# JouleMeter_new.net
KiCad netlist of a schematic drawn in EAGLE
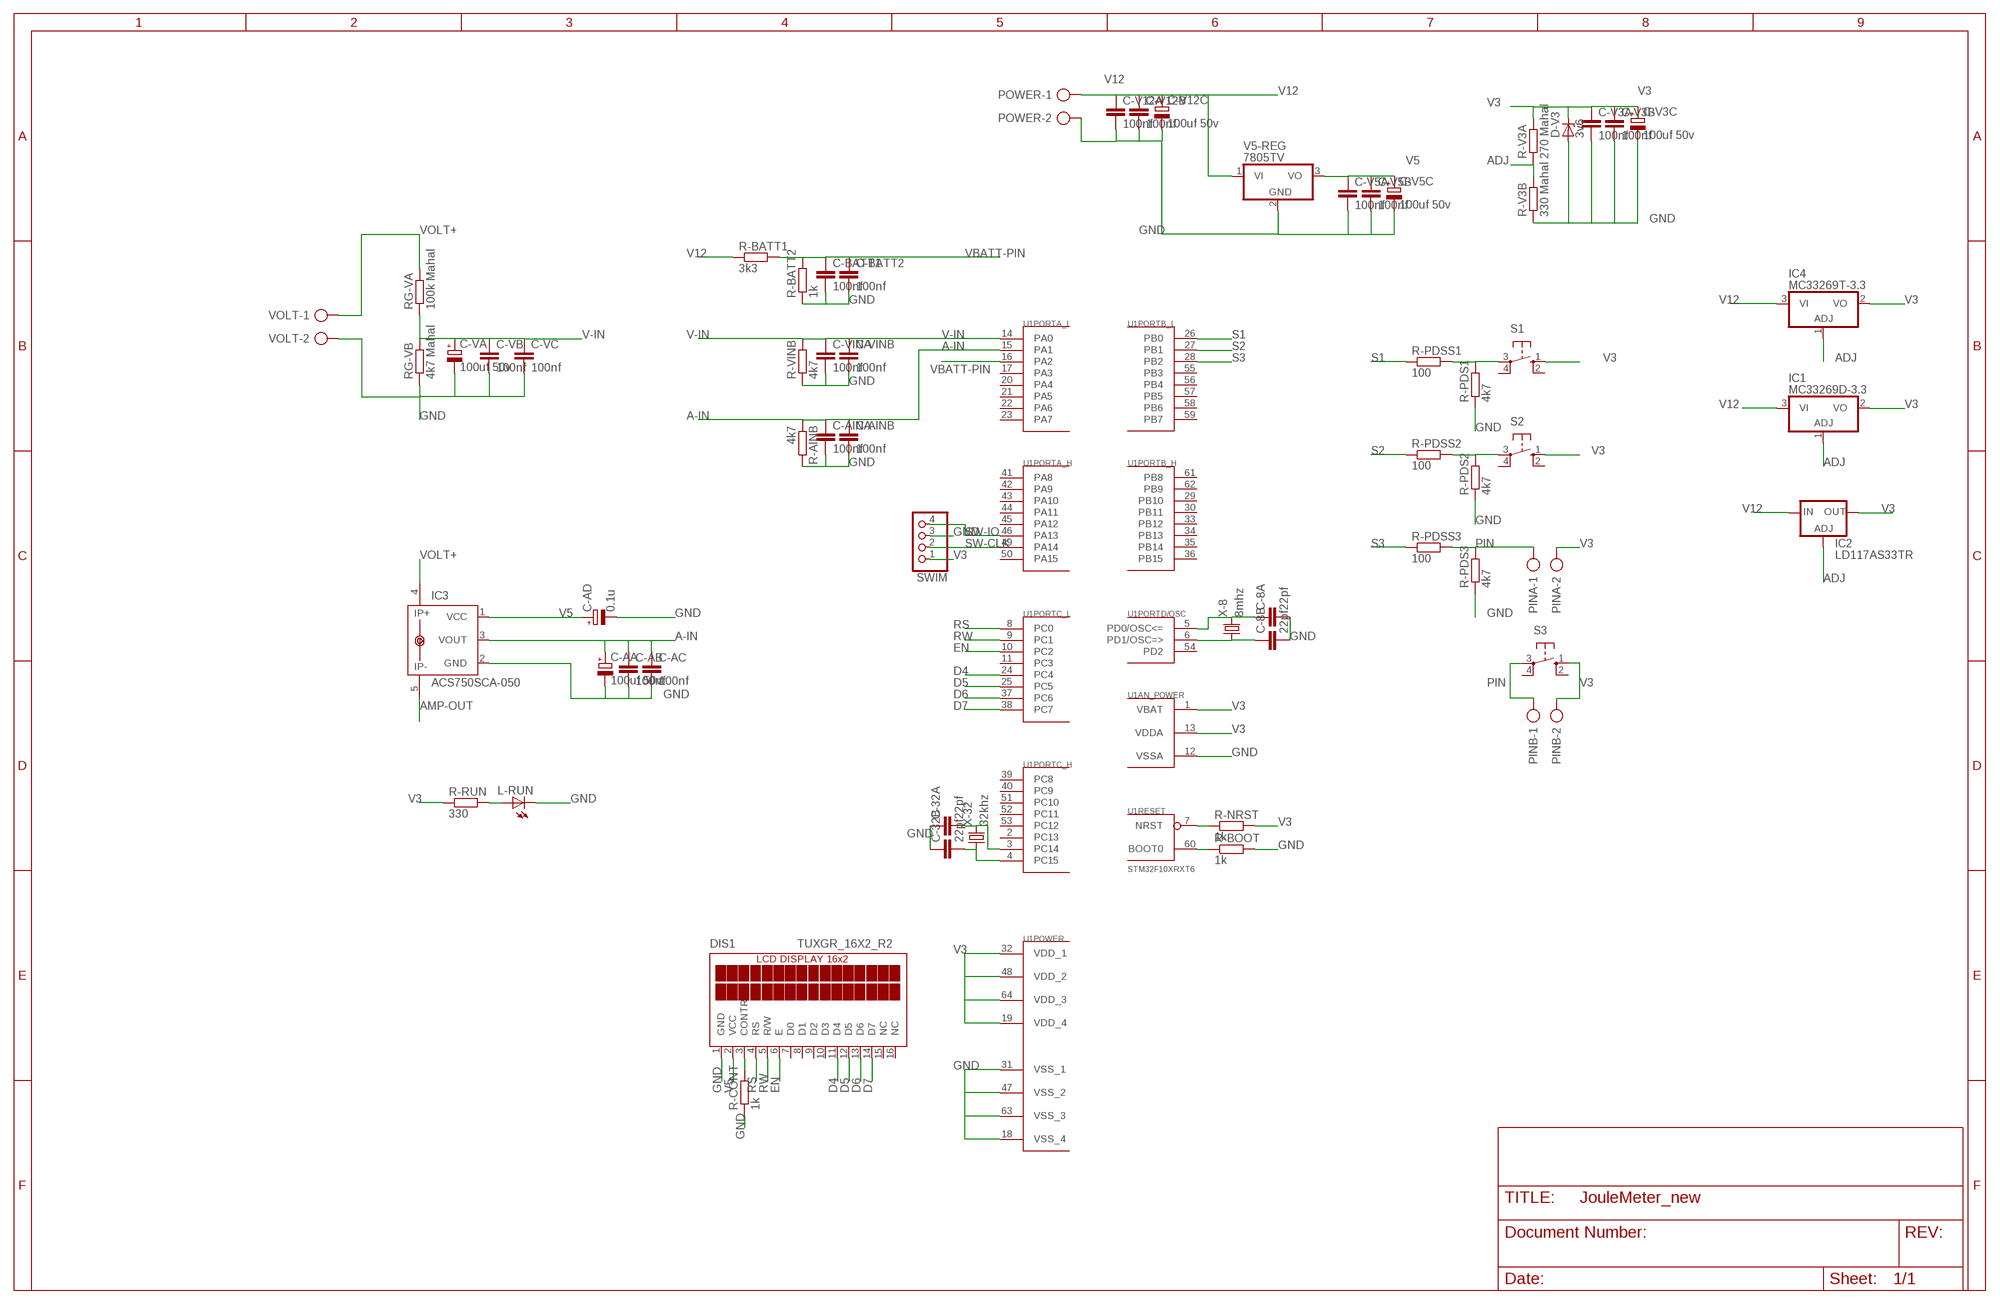
[diagram p0: schematic, sheet 1]

(export (version "E")
  (design (tool "Eeschema 10.0.6"))
  (components
    (comp (ref "C-8A")
      (value "22pf")
      (footprint "eagle-import:C025-024X044")
      (libsource (lib "eagle-import") (part "C-EU025-024X044"))
    )
    (comp (ref "C-8B")
      (value "22pf")
      (footprint "eagle-import:C025-024X044")
      (libsource (lib "eagle-import") (part "C-EU025-024X044"))
    )
    (comp (ref "C-32A")
      (value "22pf")
      (footprint "eagle-import:C025-024X044")
      (libsource (lib "eagle-import") (part "C-EU025-024X044"))
    )
    (comp (ref "C-32B")
      (value "22pf")
      (footprint "eagle-import:C025-024X044")
      (libsource (lib "eagle-import") (part "C-EU025-024X044"))
    )
    (comp (ref "C-AA")
      (value "100uf 50v")
      (footprint "eagle-import:E2-5")
      (libsource (lib "eagle-import") (part "CPOL-EUE2-5"))
    )
    (comp (ref "C-AB")
      (value "100nf")
      (footprint "eagle-import:C050-024X044")
      (libsource (lib "eagle-import") (part "C-EU050-024X044"))
    )
    (comp (ref "C-AC")
      (value "100nf")
      (footprint "eagle-import:C050-024X044")
      (libsource (lib "eagle-import") (part "C-EU050-024X044"))
    )
    (comp (ref "C-AD")
      (value "0.1u")
      (footprint "eagle-import:E2-5")
      (libsource (lib "eagle-import") (part "CPOL-EUE2-5"))
    )
    (comp (ref "C-AINA")
      (value "100nf")
      (footprint "eagle-import:C050-024X044")
      (libsource (lib "eagle-import") (part "C-EU050-024X044"))
    )
    (comp (ref "C-AINB")
      (value "100nf")
      (footprint "eagle-import:C050-024X044")
      (libsource (lib "eagle-import") (part "C-EU050-024X044"))
    )
    (comp (ref "C-BATT1")
      (value "100nf")
      (footprint "eagle-import:C050-024X044")
      (libsource (lib "eagle-import") (part "C-EU050-024X044"))
    )
    (comp (ref "C-BATT2")
      (value "100nf")
      (footprint "eagle-import:C050-024X044")
      (libsource (lib "eagle-import") (part "C-EU050-024X044"))
    )
    (comp (ref "C-V3A")
      (value "100nf")
      (footprint "eagle-import:C050-024X044")
      (libsource (lib "eagle-import") (part "C-EU050-024X044"))
    )
    (comp (ref "C-V3B")
      (value "100nf")
      (footprint "eagle-import:C050-024X044")
      (libsource (lib "eagle-import") (part "C-EU050-024X044"))
    )
    (comp (ref "C-V3C")
      (value "100uf 50v")
      (footprint "eagle-import:E5-5")
      (libsource (lib "eagle-import") (part "CPOL-EUE5-5"))
    )
    (comp (ref "C-V5A")
      (value "100nf")
      (footprint "eagle-import:C050-024X044")
      (libsource (lib "eagle-import") (part "C-EU050-024X044"))
    )
    (comp (ref "C-V5B")
      (value "100nf")
      (footprint "eagle-import:C050-024X044")
      (libsource (lib "eagle-import") (part "C-EU050-024X044"))
    )
    (comp (ref "C-V5C")
      (value "100uf 50v")
      (footprint "eagle-import:E5-5")
      (libsource (lib "eagle-import") (part "CPOL-EUE5-5"))
    )
    (comp (ref "C-V12A")
      (value "100nf")
      (footprint "eagle-import:C050-024X044")
      (libsource (lib "eagle-import") (part "C-EU050-024X044"))
    )
    (comp (ref "C-V12B")
      (value "100nf")
      (footprint "eagle-import:C050-024X044")
      (libsource (lib "eagle-import") (part "C-EU050-024X044"))
    )
    (comp (ref "C-V12C")
      (value "100uf 50v")
      (footprint "eagle-import:E5-5")
      (libsource (lib "eagle-import") (part "CPOL-EUE5-5"))
    )
    (comp (ref "C-VA")
      (value "100uf 50v")
      (footprint "eagle-import:E2-5")
      (libsource (lib "eagle-import") (part "CPOL-EUE2-5"))
    )
    (comp (ref "C-VB")
      (value "100nf")
      (footprint "eagle-import:C050-024X044")
      (libsource (lib "eagle-import") (part "C-EU050-024X044"))
    )
    (comp (ref "C-VC")
      (value "100nf")
      (footprint "eagle-import:C050-024X044")
      (libsource (lib "eagle-import") (part "C-EU050-024X044"))
    )
    (comp (ref "C-VINA")
      (value "100nf")
      (footprint "eagle-import:C050-024X044")
      (libsource (lib "eagle-import") (part "C-EU050-024X044"))
    )
    (comp (ref "C-VINB")
      (value "100nf")
      (footprint "eagle-import:C050-024X044")
      (libsource (lib "eagle-import") (part "C-EU050-024X044"))
    )
    (comp (ref "D-V3")
      (value "3v6")
      (footprint "eagle-import:ZDIO-7.5")
      (libsource (lib "eagle-import") (part "ZENER-DIODEZD-7.5"))
    )
    (comp (ref "DIS1")
      (value "TUXGR_16X2_R2")
      (footprint "eagle-import:TUXGR_16X2_R2")
      (libsource (lib "eagle-import") (part "TUXGR_16X2_R2"))
    )
    (comp (ref "IC1")
      (value "MC33269D-3.3")
      (footprint "eagle-import:DPACK")
      (libsource (lib "eagle-import") (part "MC33269?D-3.3"))
    )
    (comp (ref "IC2")
      (value "LD117AS33TR")
      (footprint "eagle-import:SOT223")
      (libsource (lib "eagle-import") (part "LD117A?S33TR"))
    )
    (comp (ref "IC3")
      (value "ACS750SCA-050")
      (footprint "eagle-import:ACS75050")
      (fields (field (name "MF") "ALLEGRO MICROSYSTEMS, INC."))
      (libsource (lib "eagle-import") (part "ACS750CA-050S"))
    )
    (comp (ref "IC4")
      (value "MC33269T-3.3")
      (footprint "eagle-import:TO220V")
      (libsource (lib "eagle-import") (part "MC33269?T-3.3"))
    )
    (comp (ref "L-RUN")
      (value "LED3MM")
      (footprint "eagle-import:LED3MM")
      (libsource (lib "eagle-import") (part "LED3MM"))
    )
    (comp (ref "PINA")
      (value "AK300/2")
      (footprint "eagle-import:AK300_2")
      (libsource (lib "eagle-import") (part "AK300/2"))
    )
    (comp (ref "PINB")
      (value "AK300/2")
      (footprint "eagle-import:AK300_2")
      (libsource (lib "eagle-import") (part "AK300/2"))
    )
    (comp (ref "POWER")
      (value "AK300/2")
      (footprint "eagle-import:AK300_2")
      (libsource (lib "eagle-import") (part "AK300/2"))
    )
    (comp (ref "R-AINB")
      (value "4k7")
      (footprint "eagle-import:0204_7")
      (libsource (lib "eagle-import") (part "R-EU_0204/7"))
    )
    (comp (ref "R-BATT1")
      (value "3k3")
      (footprint "eagle-import:0204_7")
      (libsource (lib "eagle-import") (part "R-EU_0204/7"))
    )
    (comp (ref "R-BATT2")
      (value "1k")
      (footprint "eagle-import:0204_7")
      (libsource (lib "eagle-import") (part "R-EU_0204/7"))
    )
    (comp (ref "R-BOOT")
      (value "1k")
      (footprint "eagle-import:0204_7")
      (libsource (lib "eagle-import") (part "R-EU_0204/7"))
    )
    (comp (ref "R-CONT")
      (value "1k")
      (footprint "eagle-import:0204_7")
      (libsource (lib "eagle-import") (part "R-EU_0204/7"))
    )
    (comp (ref "R-NRST")
      (value "1k")
      (footprint "eagle-import:0204_7")
      (libsource (lib "eagle-import") (part "R-EU_0204/7"))
    )
    (comp (ref "R-PDS1")
      (value "4k7")
      (footprint "eagle-import:0204_7")
      (libsource (lib "eagle-import") (part "R-EU_0204/7"))
    )
    (comp (ref "R-PDS2")
      (value "4k7")
      (footprint "eagle-import:0204_7")
      (libsource (lib "eagle-import") (part "R-EU_0204/7"))
    )
    (comp (ref "R-PDS3")
      (value "4k7")
      (footprint "eagle-import:0204_7")
      (libsource (lib "eagle-import") (part "R-EU_0204/7"))
    )
    (comp (ref "R-PDSS1")
      (value "100")
      (footprint "eagle-import:0204_7")
      (libsource (lib "eagle-import") (part "R-EU_0204/7"))
    )
    (comp (ref "R-PDSS2")
      (value "100")
      (footprint "eagle-import:0204_7")
      (libsource (lib "eagle-import") (part "R-EU_0204/7"))
    )
    (comp (ref "R-PDSS3")
      (value "100")
      (footprint "eagle-import:0204_7")
      (libsource (lib "eagle-import") (part "R-EU_0204/7"))
    )
    (comp (ref "R-RUN")
      (value "330")
      (footprint "eagle-import:0204_7")
      (libsource (lib "eagle-import") (part "R-EU_0204/7"))
    )
    (comp (ref "R-V3A")
      (value "270 Mahal")
      (footprint "eagle-import:0204_7")
      (libsource (lib "eagle-import") (part "R-EU_0204/7"))
    )
    (comp (ref "R-V3B")
      (value "330 Mahal")
      (footprint "eagle-import:0204_7")
      (libsource (lib "eagle-import") (part "R-EU_0204/7"))
    )
    (comp (ref "R-VINB")
      (value "4k7")
      (footprint "eagle-import:0204_7")
      (libsource (lib "eagle-import") (part "R-EU_0204/7"))
    )
    (comp (ref "RG-VA")
      (value "100k Mahal")
      (footprint "eagle-import:0204_7")
      (libsource (lib "eagle-import") (part "R-EU_0204/7"))
    )
    (comp (ref "RG-VB")
      (value "4k7 Mahal")
      (footprint "eagle-import:0204_7")
      (libsource (lib "eagle-import") (part "R-EU_0204/7"))
    )
    (comp (ref "S1")
      (value "10-XX")
      (footprint "eagle-import:B3F-10XX")
      (fields (field (name "MPN") "B3F-1000"))
      (libsource (lib "eagle-import") (part "10-XX"))
    )
    (comp (ref "S2")
      (value "10-XX")
      (footprint "eagle-import:B3F-10XX")
      (fields (field (name "MPN") "B3F-1000"))
      (libsource (lib "eagle-import") (part "10-XX"))
    )
    (comp (ref "S3")
      (value "40-XX")
      (footprint "eagle-import:B3F-40XX")
      (fields (field (name "MF") "OMRON COMPONENTS USA") (field (name "MPN") "B3F-4000"))
      (libsource (lib "eagle-import") (part "40-XX"))
    )
    (comp (ref "SWIM")
      (value "PINHD-1X4")
      (footprint "eagle-import:1X04")
      (libsource (lib "eagle-import") (part "PINHD-1X4"))
    )
    (comp (ref "U1")
      (value "STM32F10XRXT6")
      (footprint "eagle-import:TQFP64")
      (libsource (lib "eagle-import") (part "STM32F10XRXT6"))
    )
    (comp (ref "V5-REG")
      (value "7805TV")
      (footprint "eagle-import:TO220V")
      (libsource (lib "eagle-import") (part "78TV05"))
    )
    (comp (ref "VOLT")
      (value "AK300/2")
      (footprint "eagle-import:AK300_2")
      (libsource (lib "eagle-import") (part "AK300/2"))
    )
    (comp (ref "X-8")
      (value "8mhz")
      (footprint "eagle-import:HC49U-V")
      (libsource (lib "eagle-import") (part "CRYSTALHC49U-V"))
    )
    (comp (ref "X-32")
      (value "32khz")
      (footprint "eagle-import:TC26V")
      (libsource (lib "eagle-import") (part "CRYSTALTC26V"))
    )
  )
  (nets
    (net (code "1") (name "/A-IN") (class "Default")
      (node (ref "C-AA") (pin "+") (pinfunction "+_+") (pintype "passive"))
      (node (ref "C-AB") (pin "1") (pinfunction "1_1") (pintype "passive"))
      (node (ref "C-AC") (pin "1") (pinfunction "1_1") (pintype "passive"))
      (node (ref "C-AINA") (pin "1") (pinfunction "1_1") (pintype "passive"))
      (node (ref "C-AINB") (pin "1") (pinfunction "1_1") (pintype "passive"))
      (node (ref "IC3") (pin "3") (pinfunction "VOUT_3") (pintype "output"))
      (node (ref "R-AINB") (pin "1") (pinfunction "1_1") (pintype "passive"))
      (node (ref "U1") (pin "15") (pinfunction "PA1_15") (pintype "bidirectional"))
    )
    (net (code "2") (name "/ADJ") (class "Default")
      (node (ref "IC1") (pin "1") (pinfunction "ADJ_1") (pintype "input"))
      (node (ref "IC2") (pin "1") (pinfunction "ADJ_1") (pintype "input"))
      (node (ref "IC4") (pin "1") (pinfunction "ADJ_1") (pintype "input"))
      (node (ref "R-V3A") (pin "1") (pinfunction "1_1") (pintype "passive"))
      (node (ref "R-V3B") (pin "2") (pinfunction "2_2") (pintype "passive"))
    )
    (net (code "3") (name "/AMP-OUT") (class "Default")
      (node (ref "IC3") (pin "5") (pinfunction "IP-_5") (pintype "passive"))
    )
    (net (code "4") (name "/D4") (class "Default")
      (node (ref "DIS1") (pin "11") (pinfunction "D4_11") (pintype "input"))
      (node (ref "U1") (pin "24") (pinfunction "PC4_24") (pintype "bidirectional"))
    )
    (net (code "5") (name "/D5") (class "Default")
      (node (ref "DIS1") (pin "12") (pinfunction "D5_12") (pintype "input"))
      (node (ref "U1") (pin "25") (pinfunction "PC5_25") (pintype "bidirectional"))
    )
    (net (code "6") (name "/D6") (class "Default")
      (node (ref "DIS1") (pin "13") (pinfunction "D6_13") (pintype "input"))
      (node (ref "U1") (pin "37") (pinfunction "PC6_37") (pintype "bidirectional"))
    )
    (net (code "7") (name "/D7") (class "Default")
      (node (ref "DIS1") (pin "14") (pinfunction "D7_14") (pintype "input"))
      (node (ref "U1") (pin "38") (pinfunction "PC7_38") (pintype "bidirectional"))
    )
    (net (code "8") (name "/EN") (class "Default")
      (node (ref "DIS1") (pin "6") (pinfunction "E_6") (pintype "input"))
      (node (ref "U1") (pin "10") (pinfunction "PC2_10") (pintype "bidirectional"))
    )
    (net (code "9") (name "/GND") (class "Default")
      (node (ref "C-32A") (pin "1") (pinfunction "1_1") (pintype "passive"))
      (node (ref "C-32B") (pin "1") (pinfunction "1_1") (pintype "passive"))
      (node (ref "C-8A") (pin "2") (pinfunction "2_2") (pintype "passive"))
      (node (ref "C-8B") (pin "2") (pinfunction "2_2") (pintype "passive"))
      (node (ref "C-AA") (pin "-") (pinfunction "-_-") (pintype "passive"))
      (node (ref "C-AB") (pin "2") (pinfunction "2_2") (pintype "passive"))
      (node (ref "C-AC") (pin "2") (pinfunction "2_2") (pintype "passive"))
      (node (ref "C-AD") (pin "-") (pinfunction "-_-") (pintype "passive"))
      (node (ref "C-AINA") (pin "2") (pinfunction "2_2") (pintype "passive"))
      (node (ref "C-AINB") (pin "2") (pinfunction "2_2") (pintype "passive"))
      (node (ref "C-BATT1") (pin "2") (pinfunction "2_2") (pintype "passive"))
      (node (ref "C-BATT2") (pin "2") (pinfunction "2_2") (pintype "passive"))
      (node (ref "C-V12A") (pin "2") (pinfunction "2_2") (pintype "passive"))
      (node (ref "C-V12B") (pin "2") (pinfunction "2_2") (pintype "passive"))
      (node (ref "C-V12C") (pin "-") (pinfunction "-_-") (pintype "passive"))
      (node (ref "C-V3A") (pin "2") (pinfunction "2_2") (pintype "passive"))
      (node (ref "C-V3B") (pin "2") (pinfunction "2_2") (pintype "passive"))
      (node (ref "C-V3C") (pin "-") (pinfunction "-_-") (pintype "passive"))
      (node (ref "C-V5A") (pin "2") (pinfunction "2_2") (pintype "passive"))
      (node (ref "C-V5B") (pin "2") (pinfunction "2_2") (pintype "passive"))
      (node (ref "C-V5C") (pin "-") (pinfunction "-_-") (pintype "passive"))
      (node (ref "C-VA") (pin "-") (pinfunction "-_-") (pintype "passive"))
      (node (ref "C-VB") (pin "2") (pinfunction "2_2") (pintype "passive"))
      (node (ref "C-VC") (pin "2") (pinfunction "2_2") (pintype "passive"))
      (node (ref "C-VINA") (pin "2") (pinfunction "2_2") (pintype "passive"))
      (node (ref "C-VINB") (pin "2") (pinfunction "2_2") (pintype "passive"))
      (node (ref "D-V3") (pin "A") (pinfunction "A_A") (pintype "passive"))
      (node (ref "DIS1") (pin "1") (pinfunction "GND_1") (pintype "power_in"))
      (node (ref "IC3") (pin "2") (pinfunction "GND_2") (pintype "power_in"))
      (node (ref "L-RUN") (pin "K") (pinfunction "C_K") (pintype "passive"))
      (node (ref "POWER") (pin "2") (pinfunction "KL_2") (pintype "passive"))
      (node (ref "R-AINB") (pin "2") (pinfunction "2_2") (pintype "passive"))
      (node (ref "R-BATT2") (pin "1") (pinfunction "1_1") (pintype "passive"))
      (node (ref "R-BOOT") (pin "2") (pinfunction "2_2") (pintype "passive"))
      (node (ref "R-CONT") (pin "1") (pinfunction "1_1") (pintype "passive"))
      (node (ref "R-PDS1") (pin "1") (pinfunction "1_1") (pintype "passive"))
      (node (ref "R-PDS2") (pin "1") (pinfunction "1_1") (pintype "passive"))
      (node (ref "R-PDS3") (pin "1") (pinfunction "1_1") (pintype "passive"))
      (node (ref "R-V3B") (pin "1") (pinfunction "1_1") (pintype "passive"))
      (node (ref "R-VINB") (pin "1") (pinfunction "1_1") (pintype "passive"))
      (node (ref "RG-VB") (pin "1") (pinfunction "1_1") (pintype "passive"))
      (node (ref "SWIM") (pin "3") (pinfunction "3_3") (pintype "passive"))
      (node (ref "U1") (pin "12") (pinfunction "VSSA_12") (pintype "power_in"))
      (node (ref "U1") (pin "18") (pinfunction "VSS_4_18") (pintype "power_in"))
      (node (ref "U1") (pin "31") (pinfunction "VSS_1_31") (pintype "power_in"))
      (node (ref "U1") (pin "47") (pinfunction "VSS_2_47") (pintype "power_in"))
      (node (ref "U1") (pin "63") (pinfunction "VSS_3_63") (pintype "power_in"))
      (node (ref "V5-REG") (pin "2") (pinfunction "GND_2") (pintype "passive"))
      (node (ref "VOLT") (pin "2") (pinfunction "KL_2") (pintype "passive"))
    )
    (net (code "10") (name "/PIN") (class "Default")
      (node (ref "PINA") (pin "1") (pinfunction "KL_1") (pintype "passive"))
      (node (ref "PINB") (pin "1") (pinfunction "KL_1") (pintype "passive"))
      (node (ref "R-PDS3") (pin "2") (pinfunction "2_2") (pintype "passive"))
      (node (ref "R-PDSS3") (pin "2") (pinfunction "2_2") (pintype "passive"))
      (node (ref "S3") (pin "3") (pinfunction "P_3") (pintype "passive"))
    )
    (net (code "11") (name "/RS") (class "Default")
      (node (ref "DIS1") (pin "4") (pinfunction "RS_4") (pintype "input"))
      (node (ref "U1") (pin "8") (pinfunction "PC0_8") (pintype "bidirectional"))
    )
    (net (code "12") (name "/RW") (class "Default")
      (node (ref "DIS1") (pin "5") (pinfunction "R/W_5") (pintype "input"))
      (node (ref "U1") (pin "9") (pinfunction "PC1_9") (pintype "bidirectional"))
    )
    (net (code "13") (name "/S1") (class "Default")
      (node (ref "R-PDSS1") (pin "1") (pinfunction "1_1") (pintype "passive"))
      (node (ref "U1") (pin "26") (pinfunction "PB0_26") (pintype "bidirectional"))
    )
    (net (code "14") (name "/S2") (class "Default")
      (node (ref "R-PDSS2") (pin "1") (pinfunction "1_1") (pintype "passive"))
      (node (ref "U1") (pin "27") (pinfunction "PB1_27") (pintype "bidirectional"))
    )
    (net (code "15") (name "/S3") (class "Default")
      (node (ref "R-PDSS3") (pin "1") (pinfunction "1_1") (pintype "passive"))
      (node (ref "U1") (pin "28") (pinfunction "PB2_28") (pintype "bidirectional"))
    )
    (net (code "16") (name "/SW-CLK") (class "Default")
      (node (ref "SWIM") (pin "2") (pinfunction "2_2") (pintype "passive"))
      (node (ref "U1") (pin "49") (pinfunction "PA14_49") (pintype "bidirectional"))
    )
    (net (code "17") (name "/SW-IO") (class "Default")
      (node (ref "SWIM") (pin "4") (pinfunction "4_4") (pintype "passive"))
      (node (ref "U1") (pin "46") (pinfunction "PA13_46") (pintype "bidirectional"))
    )
    (net (code "18") (name "/V-IN") (class "Default")
      (node (ref "C-VA") (pin "+") (pinfunction "+_+") (pintype "passive"))
      (node (ref "C-VB") (pin "1") (pinfunction "1_1") (pintype "passive"))
      (node (ref "C-VC") (pin "1") (pinfunction "1_1") (pintype "passive"))
      (node (ref "C-VINA") (pin "1") (pinfunction "1_1") (pintype "passive"))
      (node (ref "C-VINB") (pin "1") (pinfunction "1_1") (pintype "passive"))
      (node (ref "R-VINB") (pin "2") (pinfunction "2_2") (pintype "passive"))
      (node (ref "RG-VA") (pin "1") (pinfunction "1_1") (pintype "passive"))
      (node (ref "RG-VB") (pin "2") (pinfunction "2_2") (pintype "passive"))
      (node (ref "U1") (pin "14") (pinfunction "PA0_14") (pintype "bidirectional"))
    )
    (net (code "19") (name "/V3") (class "Default")
      (node (ref "C-V3A") (pin "1") (pinfunction "1_1") (pintype "passive"))
      (node (ref "C-V3B") (pin "1") (pinfunction "1_1") (pintype "passive"))
      (node (ref "C-V3C") (pin "+") (pinfunction "+_+") (pintype "passive"))
      (node (ref "D-V3") (pin "C") (pinfunction "C_C") (pintype "passive"))
      (node (ref "IC1") (pin "2") (pinfunction "VO_2") (pintype "passive"))
      (node (ref "IC2") (pin "4") (pinfunction "OUT_4") (pintype "passive"))
      (node (ref "IC4") (pin "2") (pinfunction "VO_2") (pintype "passive"))
      (node (ref "PINA") (pin "2") (pinfunction "KL_2") (pintype "passive"))
      (node (ref "PINB") (pin "2") (pinfunction "KL_2") (pintype "passive"))
      (node (ref "R-NRST") (pin "2") (pinfunction "2_2") (pintype "passive"))
      (node (ref "R-RUN") (pin "1") (pinfunction "1_1") (pintype "passive"))
      (node (ref "R-V3A") (pin "2") (pinfunction "2_2") (pintype "passive"))
      (node (ref "S1") (pin "1") (pinfunction "S_1") (pintype "passive"))
      (node (ref "S2") (pin "1") (pinfunction "S_1") (pintype "passive"))
      (node (ref "S3") (pin "1") (pinfunction "S_1") (pintype "passive"))
      (node (ref "SWIM") (pin "1") (pinfunction "1_1") (pintype "passive"))
      (node (ref "U1") (pin "1") (pinfunction "VBAT_1") (pintype "power_in"))
      (node (ref "U1") (pin "13") (pinfunction "VDDA_13") (pintype "power_in"))
      (node (ref "U1") (pin "19") (pinfunction "VDD_4_19") (pintype "power_in"))
      (node (ref "U1") (pin "32") (pinfunction "VDD_1_32") (pintype "power_in"))
      (node (ref "U1") (pin "48") (pinfunction "VDD_2_48") (pintype "power_in"))
      (node (ref "U1") (pin "64") (pinfunction "VDD_3_64") (pintype "power_in"))
    )
    (net (code "20") (name "/V5") (class "Default")
      (node (ref "C-AD") (pin "+") (pinfunction "+_+") (pintype "passive"))
      (node (ref "C-V5A") (pin "1") (pinfunction "1_1") (pintype "passive"))
      (node (ref "C-V5B") (pin "1") (pinfunction "1_1") (pintype "passive"))
      (node (ref "C-V5C") (pin "+") (pinfunction "+_+") (pintype "passive"))
      (node (ref "DIS1") (pin "2") (pinfunction "VCC_2") (pintype "power_in"))
      (node (ref "IC3") (pin "1") (pinfunction "VCC_1") (pintype "power_in"))
      (node (ref "V5-REG") (pin "3") (pinfunction "VO_3") (pintype "passive"))
    )
    (net (code "21") (name "/V12") (class "Default")
      (node (ref "C-V12A") (pin "1") (pinfunction "1_1") (pintype "passive"))
      (node (ref "C-V12B") (pin "1") (pinfunction "1_1") (pintype "passive"))
      (node (ref "C-V12C") (pin "+") (pinfunction "+_+") (pintype "passive"))
      (node (ref "IC1") (pin "3") (pinfunction "VI_3") (pintype "input"))
      (node (ref "IC2") (pin "3") (pinfunction "IN_3") (pintype "input"))
      (node (ref "IC4") (pin "3") (pinfunction "VI_3") (pintype "input"))
      (node (ref "POWER") (pin "1") (pinfunction "KL_1") (pintype "passive"))
      (node (ref "R-BATT1") (pin "1") (pinfunction "1_1") (pintype "passive"))
      (node (ref "V5-REG") (pin "1") (pinfunction "VI_1") (pintype "input"))
    )
    (net (code "22") (name "/VBATT-PIN") (class "Default")
      (node (ref "C-BATT1") (pin "1") (pinfunction "1_1") (pintype "passive"))
      (node (ref "C-BATT2") (pin "1") (pinfunction "1_1") (pintype "passive"))
      (node (ref "R-BATT1") (pin "2") (pinfunction "2_2") (pintype "passive"))
      (node (ref "R-BATT2") (pin "2") (pinfunction "2_2") (pintype "passive"))
      (node (ref "U1") (pin "16") (pinfunction "PA2_16") (pintype "bidirectional"))
    )
    (net (code "23") (name "/VOLT+") (class "Default")
      (node (ref "IC3") (pin "4") (pinfunction "IP+_4") (pintype "passive"))
      (node (ref "RG-VA") (pin "2") (pinfunction "2_2") (pintype "passive"))
      (node (ref "VOLT") (pin "1") (pinfunction "KL_1") (pintype "passive"))
    )
    (net (code "24") (name "Net-(DIS1-CONTR)") (class "Default")
      (node (ref "DIS1") (pin "3") (pinfunction "CONTR_3") (pintype "input"))
      (node (ref "R-CONT") (pin "2") (pinfunction "2_2") (pintype "passive"))
    )
    (net (code "25") (name "Net-(L-RUN-PadA)") (class "Default")
      (node (ref "L-RUN") (pin "A") (pinfunction "A_A") (pintype "passive"))
      (node (ref "R-RUN") (pin "2") (pinfunction "2_2") (pintype "passive"))
    )
    (net (code "26") (name "Net-(S1-P)") (class "Default")
      (node (ref "R-PDS1") (pin "2") (pinfunction "2_2") (pintype "passive"))
      (node (ref "R-PDSS1") (pin "2") (pinfunction "2_2") (pintype "passive"))
      (node (ref "S1") (pin "3") (pinfunction "P_3") (pintype "passive"))
    )
    (net (code "27") (name "Net-(S2-P)") (class "Default")
      (node (ref "R-PDS2") (pin "2") (pinfunction "2_2") (pintype "passive"))
      (node (ref "R-PDSS2") (pin "2") (pinfunction "2_2") (pintype "passive"))
      (node (ref "S2") (pin "3") (pinfunction "P_3") (pintype "passive"))
    )
    (net (code "28") (name "Net-(U1F-PC14)") (class "Default")
      (node (ref "C-32A") (pin "2") (pinfunction "2_2") (pintype "passive"))
      (node (ref "U1") (pin "3") (pinfunction "PC14_3") (pintype "bidirectional"))
      (node (ref "X-32") (pin "2") (pinfunction "2_2") (pintype "passive"))
    )
    (net (code "29") (name "Net-(U1F-PC15)") (class "Default")
      (node (ref "C-32B") (pin "2") (pinfunction "2_2") (pintype "passive"))
      (node (ref "U1") (pin "4") (pinfunction "PC15_4") (pintype "bidirectional"))
      (node (ref "X-32") (pin "1") (pinfunction "1_1") (pintype "passive"))
    )
    (net (code "30") (name "Net-(U1H-PD0{slash}OSC<=)") (class "Default")
      (node (ref "C-8A") (pin "1") (pinfunction "1_1") (pintype "passive"))
      (node (ref "U1") (pin "5") (pinfunction "PD0/OSC<=_5") (pintype "bidirectional"))
      (node (ref "X-8") (pin "2") (pinfunction "2_2") (pintype "passive"))
    )
    (net (code "31") (name "Net-(U1H-PD1{slash}OSC=>)") (class "Default")
      (node (ref "C-8B") (pin "1") (pinfunction "1_1") (pintype "passive"))
      (node (ref "U1") (pin "6") (pinfunction "PD1/OSC=>_6") (pintype "bidirectional"))
      (node (ref "X-8") (pin "1") (pinfunction "1_1") (pintype "passive"))
    )
    (net (code "32") (name "Net-(U1J-BOOT0)") (class "Default")
      (node (ref "R-BOOT") (pin "1") (pinfunction "1_1") (pintype "passive"))
      (node (ref "U1") (pin "60") (pinfunction "BOOT0_60") (pintype "input"))
    )
    (net (code "33") (name "Net-(U1J-NRST)") (class "Default")
      (node (ref "R-NRST") (pin "1") (pinfunction "1_1") (pintype "passive"))
      (node (ref "U1") (pin "7") (pinfunction "NRST_7") (pintype "input"))
    )
    (net (code "34") (name "unconnected-(DIS1-D0-Pad7)") (class "Default")
      (node (ref "DIS1") (pin "7") (pinfunction "D0_7") (pintype "input"))
    )
    (net (code "35") (name "unconnected-(DIS1-D1-Pad8)") (class "Default")
      (node (ref "DIS1") (pin "8") (pinfunction "D1_8") (pintype "input"))
    )
    (net (code "36") (name "unconnected-(DIS1-D2-Pad9)") (class "Default")
      (node (ref "DIS1") (pin "9") (pinfunction "D2_9") (pintype "input"))
    )
    (net (code "37") (name "unconnected-(DIS1-D3-Pad10)") (class "Default")
      (node (ref "DIS1") (pin "10") (pinfunction "D3_10") (pintype "input"))
    )
    (net (code "38") (name "unconnected-(DIS1-NC-Pad15)") (class "Default")
      (node (ref "DIS1") (pin "15") (pinfunction "NC_15") (pintype "no_connect"))
    )
    (net (code "39") (name "unconnected-(DIS1-NC-Pad16)") (class "Default")
      (node (ref "DIS1") (pin "16") (pinfunction "NC_16") (pintype "no_connect"))
    )
    (net (code "40") (name "unconnected-(IC3-PadIP+1)") (class "Default")
      (node (ref "IC3") (pin "IP+1") (pinfunction "IP+1_IP+1") (pintype "input"))
    )
    (net (code "41") (name "unconnected-(IC3-PadIP-1)") (class "Default")
      (node (ref "IC3") (pin "IP-1") (pinfunction "IP-1_IP-1") (pintype "input"))
    )
    (net (code "42") (name "unconnected-(S1-P1-Pad4)") (class "Default")
      (node (ref "S1") (pin "4") (pinfunction "P1_4") (pintype "passive"))
    )
    (net (code "43") (name "unconnected-(S1-S1-Pad2)") (class "Default")
      (node (ref "S1") (pin "2") (pinfunction "S1_2") (pintype "passive"))
    )
    (net (code "44") (name "unconnected-(S2-P1-Pad4)") (class "Default")
      (node (ref "S2") (pin "4") (pinfunction "P1_4") (pintype "passive"))
    )
    (net (code "45") (name "unconnected-(S2-S1-Pad2)") (class "Default")
      (node (ref "S2") (pin "2") (pinfunction "S1_2") (pintype "passive"))
    )
    (net (code "46") (name "unconnected-(S3-P1-Pad4)") (class "Default")
      (node (ref "S3") (pin "4") (pinfunction "P1_4") (pintype "passive"))
    )
    (net (code "47") (name "unconnected-(S3-S1-Pad2)") (class "Default")
      (node (ref "S3") (pin "2") (pinfunction "S1_2") (pintype "passive"))
    )
    (net (code "48") (name "unconnected-(U1B-PA8-Pad41)") (class "Default")
      (node (ref "U1") (pin "41") (pinfunction "PA8_41") (pintype "bidirectional"))
    )
    (net (code "49") (name "unconnected-(U1B-PA9-Pad42)") (class "Default")
      (node (ref "U1") (pin "42") (pinfunction "PA9_42") (pintype "bidirectional"))
    )
    (net (code "50") (name "unconnected-(U1B-PA10-Pad43)") (class "Default")
      (node (ref "U1") (pin "43") (pinfunction "PA10_43") (pintype "bidirectional"))
    )
    (net (code "51") (name "unconnected-(U1B-PA11-Pad44)") (class "Default")
      (node (ref "U1") (pin "44") (pinfunction "PA11_44") (pintype "bidirectional"))
    )
    (net (code "52") (name "unconnected-(U1B-PA12-Pad45)") (class "Default")
      (node (ref "U1") (pin "45") (pinfunction "PA12_45") (pintype "bidirectional"))
    )
    (net (code "53") (name "unconnected-(U1B-PA15-Pad50)") (class "Default")
      (node (ref "U1") (pin "50") (pinfunction "PA15_50") (pintype "bidirectional"))
    )
    (net (code "54") (name "unconnected-(U1C-PA3-Pad17)") (class "Default")
      (node (ref "U1") (pin "17") (pinfunction "PA3_17") (pintype "bidirectional"))
    )
    (net (code "55") (name "unconnected-(U1C-PA4-Pad20)") (class "Default")
      (node (ref "U1") (pin "20") (pinfunction "PA4_20") (pintype "bidirectional"))
    )
    (net (code "56") (name "unconnected-(U1C-PA5-Pad21)") (class "Default")
      (node (ref "U1") (pin "21") (pinfunction "PA5_21") (pintype "bidirectional"))
    )
    (net (code "57") (name "unconnected-(U1C-PA6-Pad22)") (class "Default")
      (node (ref "U1") (pin "22") (pinfunction "PA6_22") (pintype "bidirectional"))
    )
    (net (code "58") (name "unconnected-(U1C-PA7-Pad23)") (class "Default")
      (node (ref "U1") (pin "23") (pinfunction "PA7_23") (pintype "bidirectional"))
    )
    (net (code "59") (name "unconnected-(U1D-PB8-Pad61)") (class "Default")
      (node (ref "U1") (pin "61") (pinfunction "PB8_61") (pintype "bidirectional"))
    )
    (net (code "60") (name "unconnected-(U1D-PB9-Pad62)") (class "Default")
      (node (ref "U1") (pin "62") (pinfunction "PB9_62") (pintype "bidirectional"))
    )
    (net (code "61") (name "unconnected-(U1D-PB10-Pad29)") (class "Default")
      (node (ref "U1") (pin "29") (pinfunction "PB10_29") (pintype "bidirectional"))
    )
    (net (code "62") (name "unconnected-(U1D-PB11-Pad30)") (class "Default")
      (node (ref "U1") (pin "30") (pinfunction "PB11_30") (pintype "bidirectional"))
    )
    (net (code "63") (name "unconnected-(U1D-PB12-Pad33)") (class "Default")
      (node (ref "U1") (pin "33") (pinfunction "PB12_33") (pintype "bidirectional"))
    )
    (net (code "64") (name "unconnected-(U1D-PB13-Pad34)") (class "Default")
      (node (ref "U1") (pin "34") (pinfunction "PB13_34") (pintype "bidirectional"))
    )
    (net (code "65") (name "unconnected-(U1D-PB14-Pad35)") (class "Default")
      (node (ref "U1") (pin "35") (pinfunction "PB14_35") (pintype "bidirectional"))
    )
    (net (code "66") (name "unconnected-(U1D-PB15-Pad36)") (class "Default")
      (node (ref "U1") (pin "36") (pinfunction "PB15_36") (pintype "bidirectional"))
    )
    (net (code "67") (name "unconnected-(U1E-PB3-Pad55)") (class "Default")
      (node (ref "U1") (pin "55") (pinfunction "PB3_55") (pintype "bidirectional"))
    )
    (net (code "68") (name "unconnected-(U1E-PB4-Pad56)") (class "Default")
      (node (ref "U1") (pin "56") (pinfunction "PB4_56") (pintype "bidirectional"))
    )
    (net (code "69") (name "unconnected-(U1E-PB5-Pad57)") (class "Default")
      (node (ref "U1") (pin "57") (pinfunction "PB5_57") (pintype "bidirectional"))
    )
    (net (code "70") (name "unconnected-(U1E-PB6-Pad58)") (class "Default")
      (node (ref "U1") (pin "58") (pinfunction "PB6_58") (pintype "bidirectional"))
    )
    (net (code "71") (name "unconnected-(U1E-PB7-Pad59)") (class "Default")
      (node (ref "U1") (pin "59") (pinfunction "PB7_59") (pintype "bidirectional"))
    )
    (net (code "72") (name "unconnected-(U1F-PC8-Pad39)") (class "Default")
      (node (ref "U1") (pin "39") (pinfunction "PC8_39") (pintype "bidirectional"))
    )
    (net (code "73") (name "unconnected-(U1F-PC9-Pad40)") (class "Default")
      (node (ref "U1") (pin "40") (pinfunction "PC9_40") (pintype "bidirectional"))
    )
    (net (code "74") (name "unconnected-(U1F-PC10-Pad51)") (class "Default")
      (node (ref "U1") (pin "51") (pinfunction "PC10_51") (pintype "bidirectional"))
    )
    (net (code "75") (name "unconnected-(U1F-PC11-Pad52)") (class "Default")
      (node (ref "U1") (pin "52") (pinfunction "PC11_52") (pintype "bidirectional"))
    )
    (net (code "76") (name "unconnected-(U1F-PC12-Pad53)") (class "Default")
      (node (ref "U1") (pin "53") (pinfunction "PC12_53") (pintype "bidirectional"))
    )
    (net (code "77") (name "unconnected-(U1F-PC13-Pad2)") (class "Default")
      (node (ref "U1") (pin "2") (pinfunction "PC13_2") (pintype "bidirectional"))
    )
    (net (code "78") (name "unconnected-(U1G-PC3-Pad11)") (class "Default")
      (node (ref "U1") (pin "11") (pinfunction "PC3_11") (pintype "bidirectional"))
    )
    (net (code "79") (name "unconnected-(U1H-PD2-Pad54)") (class "Default")
      (node (ref "U1") (pin "54") (pinfunction "PD2_54") (pintype "bidirectional"))
    )
  )
)
